# ProPrj_gzy_2025-03-24.net
KiCad netlist of a schematic drawn in EasyEDA Pro
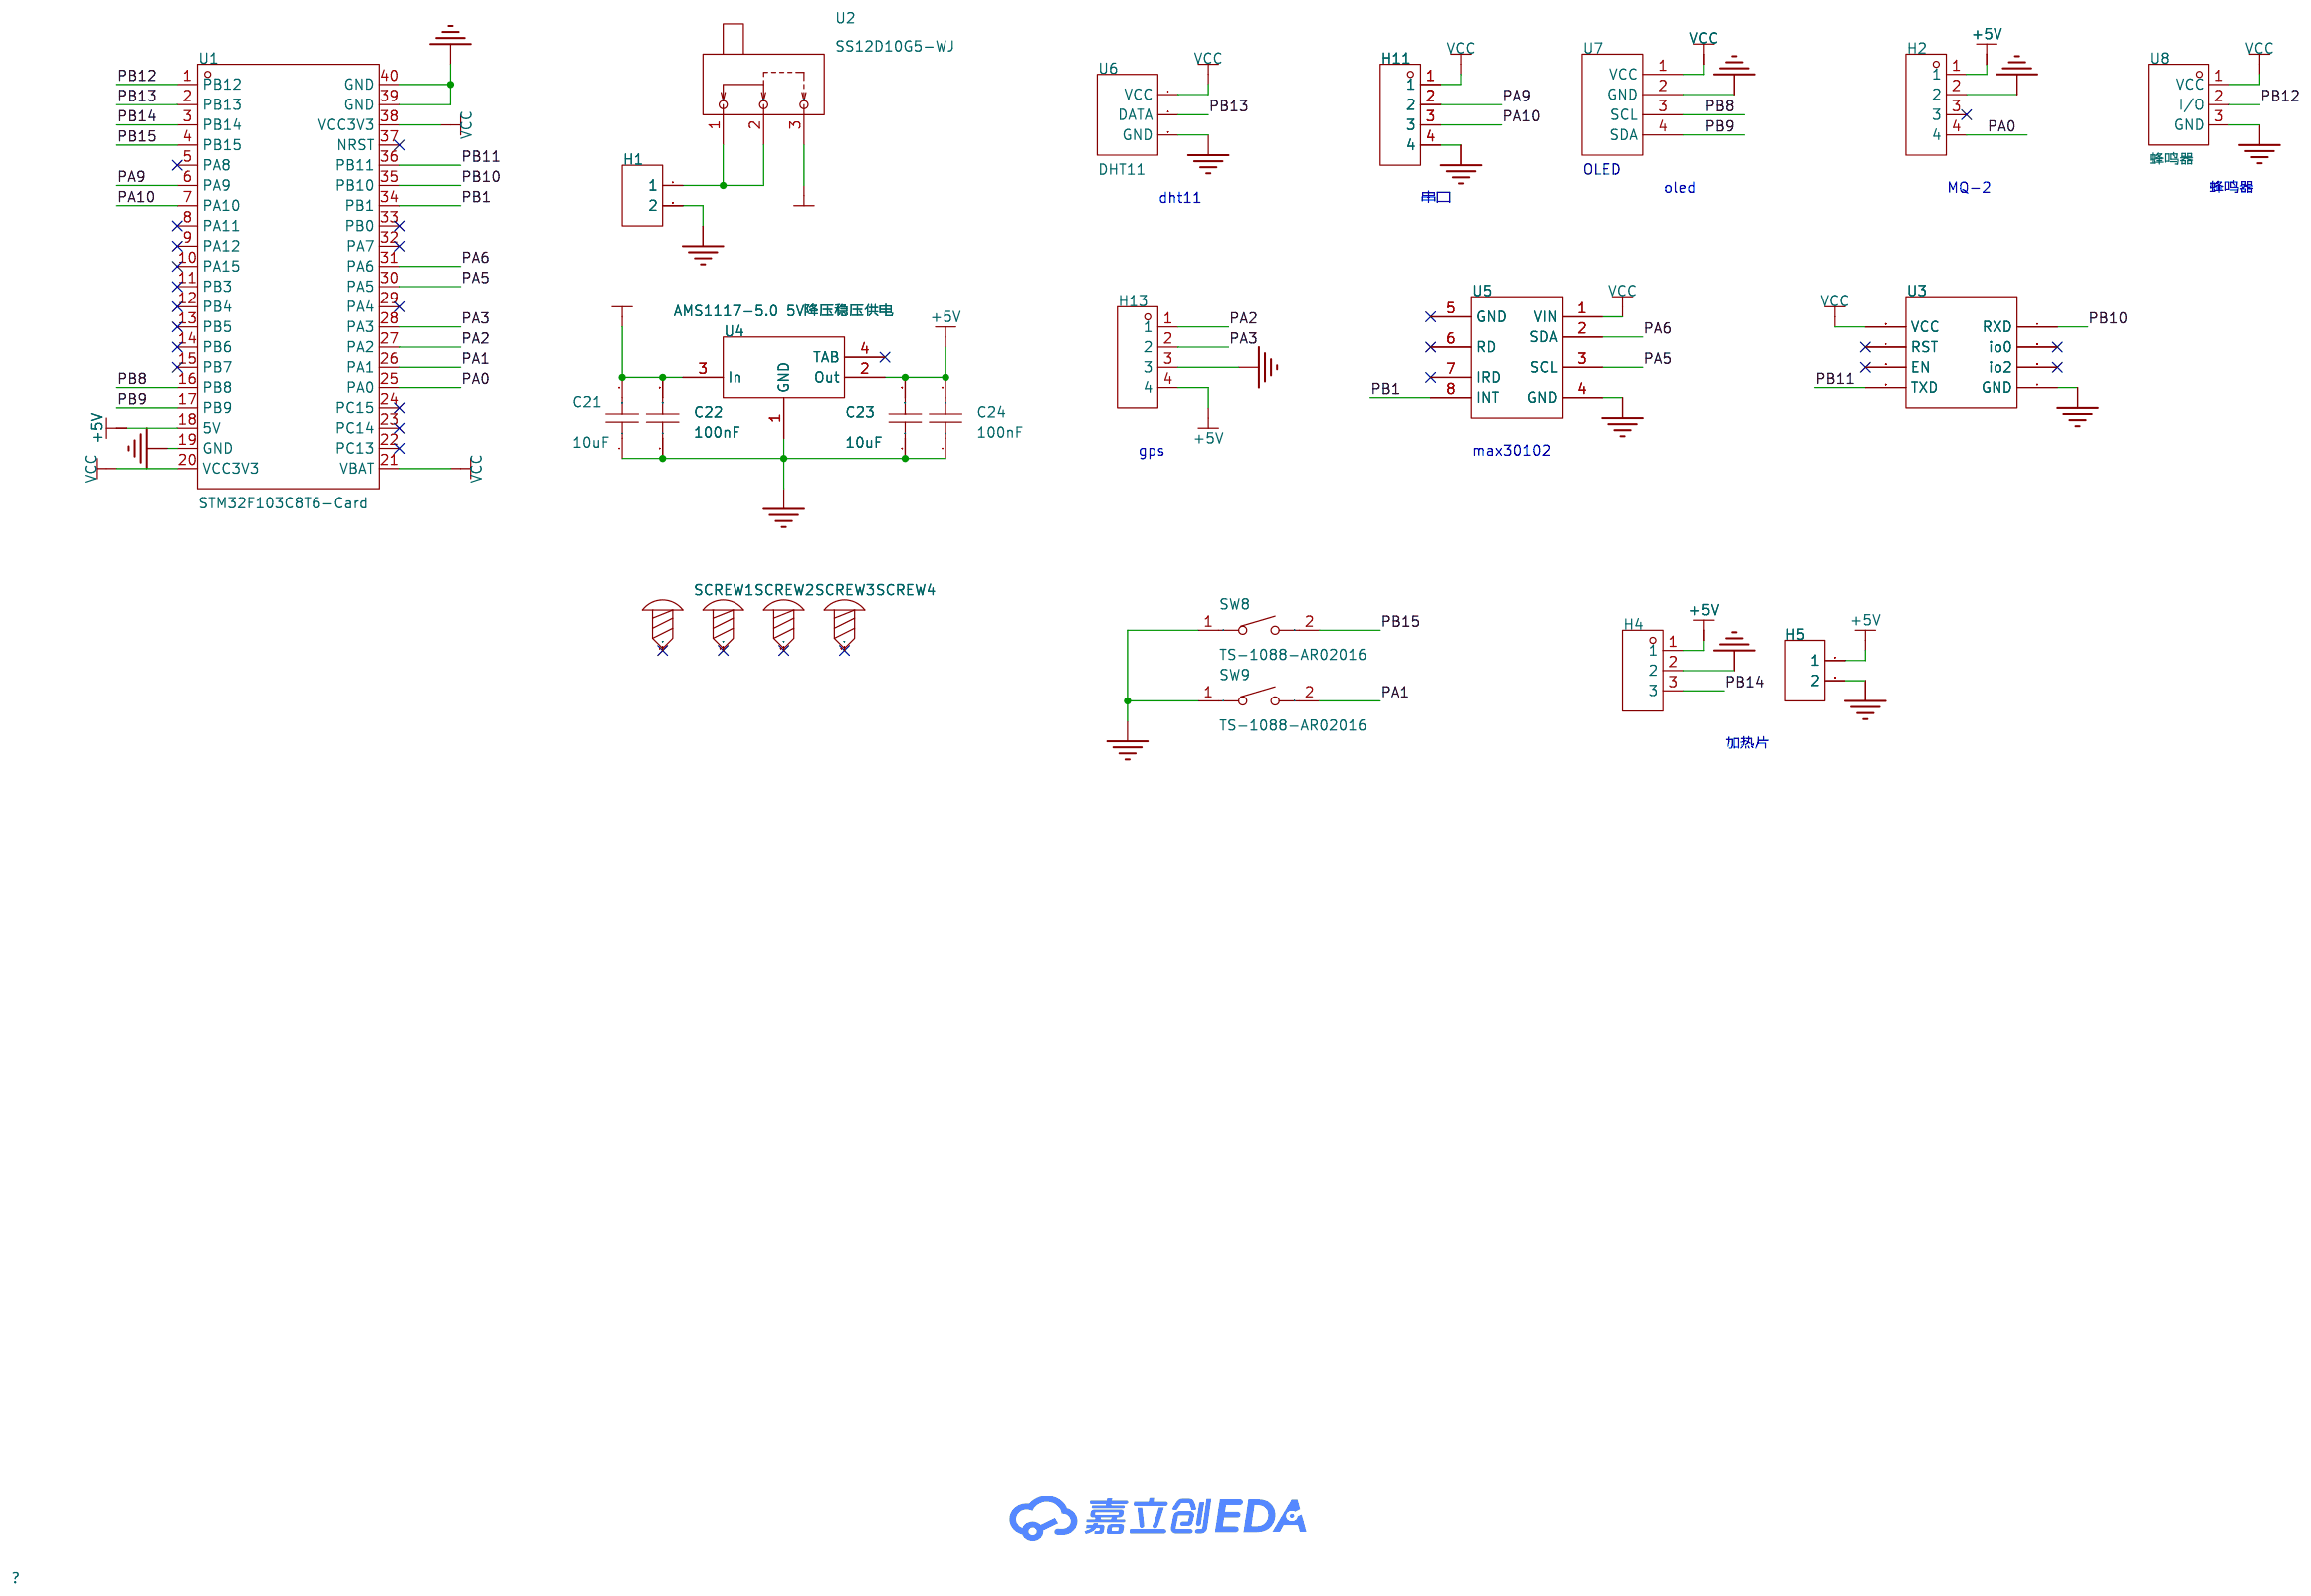
[diagram p0: schematic sheet]

(export (version "E")
  (design (tool "Eeschema 10.0.6"))
  (components
    (comp (ref "C21")
      (value "10uF")
      (footprint "easyedapro:C0805")
      (libsource (lib "easyedapro") (part "CapAcitance"))
    )
    (comp (ref "C22")
      (value "100nF")
      (footprint "easyedapro:C0805")
      (libsource (lib "easyedapro") (part "CapAcitance"))
    )
    (comp (ref "C23")
      (value "10uF")
      (footprint "easyedapro:C0805")
      (libsource (lib "easyedapro") (part "CapAcitance"))
    )
    (comp (ref "C24")
      (value "100nF")
      (footprint "easyedapro:C0805")
      (libsource (lib "easyedapro") (part "CapAcitance"))
    )
    (comp (ref "H1")
      (value "~")
      (footprint "easyedapro:HDR-TH_2P-P2.54-V-F")
      (libsource (lib "easyedapro") (part "Header-Female-2.54_1x2"))
    )
    (comp (ref "H2")
      (value "~")
      (footprint "easyedapro:HDR-TH_4P-P2.54-V-F")
      (libsource (lib "easyedapro") (part "2.54-1*4P母"))
    )
    (comp (ref "H4")
      (value "~")
      (footprint "easyedapro:HDR-TH_3P-P2.54-V-F")
      (libsource (lib "easyedapro") (part "PM254V-11-03-H85"))
    )
    (comp (ref "H5")
      (value "~")
      (footprint "easyedapro:HDR-TH_2P-P2.54-V-F")
      (libsource (lib "easyedapro") (part "Header-Female-2.54_1x2"))
    )
    (comp (ref "H11")
      (value "~")
      (footprint "easyedapro:HDR-TH_4P-P2.54-V-F")
      (libsource (lib "easyedapro") (part "2.54-1*4P母"))
    )
    (comp (ref "H13")
      (value "~")
      (footprint "easyedapro:HDR-TH_4P-P2.54-V-F")
      (libsource (lib "easyedapro") (part "2.54-1*4P母"))
    )
    (comp (ref "SCREW1")
      (value "~")
      (footprint "easyedapro:M3螺丝")
      (libsource (lib "easyedapro") (part "螺丝孔"))
    )
    (comp (ref "SCREW2")
      (value "~")
      (footprint "easyedapro:M3螺丝")
      (libsource (lib "easyedapro") (part "螺丝孔"))
    )
    (comp (ref "SCREW3")
      (value "~")
      (footprint "easyedapro:M3螺丝")
      (libsource (lib "easyedapro") (part "螺丝孔"))
    )
    (comp (ref "SCREW4")
      (value "~")
      (footprint "easyedapro:M3螺丝")
      (libsource (lib "easyedapro") (part "螺丝孔"))
    )
    (comp (ref "SW8")
      (value "TS-1088-AR02016")
      (footprint "easyedapro:SW-SMD_L3.9-W3.0-P4.45")
      (fields (field (name "Manufacturer") "XUNPU(讯普)"))
      (libsource (lib "easyedapro") (part "TS-1088-AR02016"))
    )
    (comp (ref "SW9")
      (value "TS-1088-AR02016")
      (footprint "easyedapro:SW-SMD_L3.9-W3.0-P4.45")
      (fields (field (name "Manufacturer") "XUNPU(讯普)"))
      (libsource (lib "easyedapro") (part "TS-1088-AR02016"))
    )
    (comp (ref "U1")
      (value "STM32F103C8T6-Card")
      (footprint "easyedapro:CONN-TH_L53.3-W22.9_STM32F103C8T6-CARD")
      (libsource (lib "easyedapro") (part "STM32F103C8T6-CARD"))
    )
    (comp (ref "U2")
      (value "SS12D10G5-WJ")
      (footprint "easyedapro:SW-TH_3P-SS12D06-1")
      (description "电路结构:单刀双掷;安装方式:直插;额定电流(DC):2A;额定电压(DC):125V;机械寿命:3千次;")
      (fields (field (name "Manufacturer") "SHOU HAN(首韩)"))
      (libsource (lib "easyedapro") (part "SS12D10G5-WJ"))
    )
    (comp (ref "U3")
      (value "~")
      (footprint "easyedapro:esp8266-01s")
      (description "esp8266-01swifi模块")
      (libsource (lib "easyedapro") (part "esp8266-01s"))
    )
    (comp (ref "U4")
      (value "AMS1117-5.0 5V降压稳压供电")
      (footprint "easyedapro:SOT-223_L6.5-W3.5-P2.30-LS7.0-BR")
      (fields (field (name "Manufacturer Part") "AMS1117-5.0") (field (name "Manufacturer") "AMS"))
      (libsource (lib "easyedapro") (part "AMS1117-5.0 5V降压稳压供电"))
    )
    (comp (ref "U5")
      (value "~")
      (footprint "easyedapro:MAX30102")
      (libsource (lib "easyedapro") (part "MAX30102"))
    )
    (comp (ref "U6")
      (value "DHT11")
      (footprint "easyedapro:DHT11_X")
      (libsource (lib "easyedapro") (part "DHT11"))
    )
    (comp (ref "U7")
      (value "~")
      (footprint "easyedapro:0.96OLED_4P")
      (libsource (lib "easyedapro") (part "OLED"))
    )
    (comp (ref "U8")
      (value "蜂鸣器")
      (footprint "easyedapro:蜂鸣器")
      (libsource (lib "easyedapro") (part "2.54MM间距单排插针3P/高度11MM"))
    )
  )
  (nets
    (net (code "1") (name "+5V") (class "Default")
      (node (ref "C23") (pin "2") (pinfunction "2_2") (pintype "input"))
      (node (ref "C24") (pin "2") (pinfunction "2_2") (pintype "input"))
      (node (ref "H13") (pin "4") (pinfunction "4_4") (pintype "unspecified"))
      (node (ref "H2") (pin "1") (pinfunction "1_1") (pintype "unspecified"))
      (node (ref "H4") (pin "1") (pinfunction "1_1") (pintype "unspecified"))
      (node (ref "H5") (pin "1") (pinfunction "1_1") (pintype "input"))
      (node (ref "U1") (pin "18") (pinfunction "5V_18") (pintype "unspecified"))
      (node (ref "U4") (pin "2") (pinfunction "Out_2") (pintype "input"))
    )
    (net (code "2") (name "+7V") (class "Default")
      (node (ref "C21") (pin "2") (pinfunction "2_2") (pintype "input"))
      (node (ref "C22") (pin "2") (pinfunction "2_2") (pintype "input"))
      (node (ref "U2") (pin "3") (pinfunction "3_3") (pintype "unspecified"))
      (node (ref "U4") (pin "3") (pinfunction "In_3") (pintype "input"))
    )
    (net (code "3") (name "/PA0") (class "Default")
      (node (ref "H2") (pin "4") (pinfunction "4_4") (pintype "unspecified"))
      (node (ref "U1") (pin "25") (pinfunction "PA0_25") (pintype "unspecified"))
    )
    (net (code "4") (name "/PA1") (class "Default")
      (node (ref "SW9") (pin "2") (pinfunction "2_2") (pintype "unspecified"))
      (node (ref "U1") (pin "26") (pinfunction "PA1_26") (pintype "unspecified"))
    )
    (net (code "5") (name "/PA2") (class "Default")
      (node (ref "H13") (pin "1") (pinfunction "1_1") (pintype "unspecified"))
      (node (ref "U1") (pin "27") (pinfunction "PA2_27") (pintype "unspecified"))
    )
    (net (code "6") (name "/PA3") (class "Default")
      (node (ref "H13") (pin "2") (pinfunction "2_2") (pintype "unspecified"))
      (node (ref "U1") (pin "28") (pinfunction "PA3_28") (pintype "unspecified"))
    )
    (net (code "7") (name "/PA5") (class "Default")
      (node (ref "U1") (pin "30") (pinfunction "PA5_30") (pintype "unspecified"))
      (node (ref "U5") (pin "3") (pinfunction "SCL_3") (pintype "input"))
    )
    (net (code "8") (name "/PA6") (class "Default")
      (node (ref "U1") (pin "31") (pinfunction "PA6_31") (pintype "unspecified"))
      (node (ref "U5") (pin "2") (pinfunction "SDA_2") (pintype "input"))
    )
    (net (code "9") (name "/PA9") (class "Default")
      (node (ref "H11") (pin "2") (pinfunction "2_2") (pintype "unspecified"))
      (node (ref "U1") (pin "6") (pinfunction "PA9_6") (pintype "unspecified"))
    )
    (net (code "10") (name "/PA10") (class "Default")
      (node (ref "H11") (pin "3") (pinfunction "3_3") (pintype "unspecified"))
      (node (ref "U1") (pin "7") (pinfunction "PA10_7") (pintype "unspecified"))
    )
    (net (code "11") (name "/PB1") (class "Default")
      (node (ref "U1") (pin "34") (pinfunction "PB1_34") (pintype "unspecified"))
      (node (ref "U5") (pin "8") (pinfunction "INT_8") (pintype "input"))
    )
    (net (code "12") (name "/PB8") (class "Default")
      (node (ref "U1") (pin "16") (pinfunction "PB8_16") (pintype "unspecified"))
      (node (ref "U7") (pin "3") (pinfunction "SCL_3") (pintype "input"))
    )
    (net (code "13") (name "/PB9") (class "Default")
      (node (ref "U1") (pin "17") (pinfunction "PB9_17") (pintype "unspecified"))
      (node (ref "U7") (pin "4") (pinfunction "SDA_4") (pintype "input"))
    )
    (net (code "14") (name "/PB10") (class "Default")
      (node (ref "U1") (pin "35") (pinfunction "PB10_35") (pintype "unspecified"))
      (node (ref "U3") (pin "4") (pinfunction "RXD_4") (pintype "input"))
    )
    (net (code "15") (name "/PB11") (class "Default")
      (node (ref "U1") (pin "36") (pinfunction "PB11_36") (pintype "unspecified"))
      (node (ref "U3") (pin "5") (pinfunction "TXD_5") (pintype "input"))
    )
    (net (code "16") (name "/PB12") (class "Default")
      (node (ref "U1") (pin "1") (pinfunction "PB12_1") (pintype "unspecified"))
      (node (ref "U8") (pin "2") (pinfunction "I/O_2") (pintype "input"))
    )
    (net (code "17") (name "/PB13") (class "Default")
      (node (ref "U1") (pin "2") (pinfunction "PB13_2") (pintype "unspecified"))
      (node (ref "U6") (pin "2") (pinfunction "DATA_2") (pintype "input"))
    )
    (net (code "18") (name "/PB14") (class "Default")
      (node (ref "H4") (pin "3") (pinfunction "3_3") (pintype "unspecified"))
      (node (ref "U1") (pin "3") (pinfunction "PB14_3") (pintype "unspecified"))
    )
    (net (code "19") (name "/PB15") (class "Default")
      (node (ref "SW8") (pin "2") (pinfunction "2_2") (pintype "unspecified"))
      (node (ref "U1") (pin "4") (pinfunction "PB15_4") (pintype "unspecified"))
    )
    (net (code "20") (name "GND") (class "Default")
      (node (ref "C21") (pin "1") (pinfunction "1_1") (pintype "input"))
      (node (ref "C22") (pin "1") (pinfunction "1_1") (pintype "input"))
      (node (ref "C23") (pin "1") (pinfunction "1_1") (pintype "input"))
      (node (ref "C24") (pin "1") (pinfunction "1_1") (pintype "input"))
      (node (ref "H1") (pin "2") (pinfunction "2_2") (pintype "input"))
      (node (ref "H11") (pin "4") (pinfunction "4_4") (pintype "unspecified"))
      (node (ref "H13") (pin "3") (pinfunction "3_3") (pintype "unspecified"))
      (node (ref "H2") (pin "2") (pinfunction "2_2") (pintype "unspecified"))
      (node (ref "H4") (pin "2") (pinfunction "2_2") (pintype "unspecified"))
      (node (ref "H5") (pin "2") (pinfunction "2_2") (pintype "input"))
      (node (ref "SW8") (pin "1") (pinfunction "1_1") (pintype "unspecified"))
      (node (ref "SW9") (pin "1") (pinfunction "1_1") (pintype "unspecified"))
      (node (ref "U1") (pin "19") (pinfunction "GND_19") (pintype "unspecified"))
      (node (ref "U1") (pin "39") (pinfunction "GND_39") (pintype "unspecified"))
      (node (ref "U1") (pin "40") (pinfunction "GND_40") (pintype "unspecified"))
      (node (ref "U3") (pin "1") (pinfunction "GND_1") (pintype "input"))
      (node (ref "U4") (pin "1") (pinfunction "GND_1") (pintype "input"))
      (node (ref "U5") (pin "4") (pinfunction "GND_4") (pintype "input"))
      (node (ref "U6") (pin "3") (pinfunction "GND_3") (pintype "input"))
      (node (ref "U7") (pin "2") (pinfunction "GND_2") (pintype "input"))
      (node (ref "U8") (pin "3") (pinfunction "GND_3") (pintype "input"))
    )
    (net (code "21") (name "Net-(H1-Pad1)") (class "Default")
      (node (ref "H1") (pin "1") (pinfunction "1_1") (pintype "input"))
      (node (ref "U2") (pin "1") (pinfunction "1_1") (pintype "unspecified"))
      (node (ref "U2") (pin "2") (pinfunction "2_2") (pintype "unspecified"))
    )
    (net (code "22") (name "VCC") (class "Default")
      (node (ref "H11") (pin "1") (pinfunction "1_1") (pintype "unspecified"))
      (node (ref "U1") (pin "20") (pinfunction "VCC3V3_20") (pintype "unspecified"))
      (node (ref "U1") (pin "21") (pinfunction "VBAT_21") (pintype "unspecified"))
      (node (ref "U1") (pin "38") (pinfunction "VCC3V3_38") (pintype "unspecified"))
      (node (ref "U3") (pin "8") (pinfunction "VCC_8") (pintype "input"))
      (node (ref "U5") (pin "1") (pinfunction "VIN_1") (pintype "input"))
      (node (ref "U6") (pin "1") (pinfunction "VCC_1") (pintype "input"))
      (node (ref "U7") (pin "1") (pinfunction "VCC_1") (pintype "input"))
      (node (ref "U8") (pin "1") (pinfunction "VCC_1") (pintype "input"))
    )
    (net (code "23") (name "unconnected-(H2-Pad3)") (class "Default")
      (node (ref "H2") (pin "3") (pinfunction "3_3") (pintype "unspecified+no_connect"))
    )
    (net (code "24") (name "unconnected-(SCREW1-Pad1)") (class "Default")
      (node (ref "SCREW1") (pin "1") (pinfunction "1_1") (pintype "input+no_connect"))
    )
    (net (code "25") (name "unconnected-(SCREW2-Pad1)") (class "Default")
      (node (ref "SCREW2") (pin "1") (pinfunction "1_1") (pintype "input+no_connect"))
    )
    (net (code "26") (name "unconnected-(SCREW3-Pad1)") (class "Default")
      (node (ref "SCREW3") (pin "1") (pinfunction "1_1") (pintype "input+no_connect"))
    )
    (net (code "27") (name "unconnected-(SCREW4-Pad1)") (class "Default")
      (node (ref "SCREW4") (pin "1") (pinfunction "1_1") (pintype "input+no_connect"))
    )
    (net (code "28") (name "unconnected-(U1-NRST-Pad37)") (class "Default")
      (node (ref "U1") (pin "37") (pinfunction "NRST_37") (pintype "unspecified+no_connect"))
    )
    (net (code "29") (name "unconnected-(U1-PA4-Pad29)") (class "Default")
      (node (ref "U1") (pin "29") (pinfunction "PA4_29") (pintype "unspecified+no_connect"))
    )
    (net (code "30") (name "unconnected-(U1-PA7-Pad32)") (class "Default")
      (node (ref "U1") (pin "32") (pinfunction "PA7_32") (pintype "unspecified+no_connect"))
    )
    (net (code "31") (name "unconnected-(U1-PA8-Pad5)") (class "Default")
      (node (ref "U1") (pin "5") (pinfunction "PA8_5") (pintype "unspecified+no_connect"))
    )
    (net (code "32") (name "unconnected-(U1-PA11-Pad8)") (class "Default")
      (node (ref "U1") (pin "8") (pinfunction "PA11_8") (pintype "unspecified+no_connect"))
    )
    (net (code "33") (name "unconnected-(U1-PA12-Pad9)") (class "Default")
      (node (ref "U1") (pin "9") (pinfunction "PA12_9") (pintype "unspecified+no_connect"))
    )
    (net (code "34") (name "unconnected-(U1-PA15-Pad10)") (class "Default")
      (node (ref "U1") (pin "10") (pinfunction "PA15_10") (pintype "unspecified+no_connect"))
    )
    (net (code "35") (name "unconnected-(U1-PB0-Pad33)") (class "Default")
      (node (ref "U1") (pin "33") (pinfunction "PB0_33") (pintype "unspecified+no_connect"))
    )
    (net (code "36") (name "unconnected-(U1-PB3-Pad11)") (class "Default")
      (node (ref "U1") (pin "11") (pinfunction "PB3_11") (pintype "unspecified+no_connect"))
    )
    (net (code "37") (name "unconnected-(U1-PB4-Pad12)") (class "Default")
      (node (ref "U1") (pin "12") (pinfunction "PB4_12") (pintype "unspecified+no_connect"))
    )
    (net (code "38") (name "unconnected-(U1-PB5-Pad13)") (class "Default")
      (node (ref "U1") (pin "13") (pinfunction "PB5_13") (pintype "unspecified+no_connect"))
    )
    (net (code "39") (name "unconnected-(U1-PB6-Pad14)") (class "Default")
      (node (ref "U1") (pin "14") (pinfunction "PB6_14") (pintype "unspecified+no_connect"))
    )
    (net (code "40") (name "unconnected-(U1-PB7-Pad15)") (class "Default")
      (node (ref "U1") (pin "15") (pinfunction "PB7_15") (pintype "unspecified+no_connect"))
    )
    (net (code "41") (name "unconnected-(U1-PC13-Pad22)") (class "Default")
      (node (ref "U1") (pin "22") (pinfunction "PC13_22") (pintype "unspecified+no_connect"))
    )
    (net (code "42") (name "unconnected-(U1-PC14-Pad23)") (class "Default")
      (node (ref "U1") (pin "23") (pinfunction "PC14_23") (pintype "unspecified+no_connect"))
    )
    (net (code "43") (name "unconnected-(U1-PC15-Pad24)") (class "Default")
      (node (ref "U1") (pin "24") (pinfunction "PC15_24") (pintype "unspecified+no_connect"))
    )
    (net (code "44") (name "unconnected-(U3-EN-Pad6)") (class "Default")
      (node (ref "U3") (pin "6") (pinfunction "EN_6") (pintype "input+no_connect"))
    )
    (net (code "45") (name "unconnected-(U3-RST-Pad7)") (class "Default")
      (node (ref "U3") (pin "7") (pinfunction "RST_7") (pintype "input+no_connect"))
    )
    (net (code "46") (name "unconnected-(U3-io0-Pad3)") (class "Default")
      (node (ref "U3") (pin "3") (pinfunction "io0_3") (pintype "input+no_connect"))
    )
    (net (code "47") (name "unconnected-(U3-io2-Pad2)") (class "Default")
      (node (ref "U3") (pin "2") (pinfunction "io2_2") (pintype "input+no_connect"))
    )
    (net (code "48") (name "unconnected-(U4-TAB-Pad4)") (class "Default")
      (node (ref "U4") (pin "4") (pinfunction "TAB_4") (pintype "input+no_connect"))
    )
    (net (code "49") (name "unconnected-(U5-GND-Pad5)") (class "Default")
      (node (ref "U5") (pin "5") (pinfunction "GND_5") (pintype "input+no_connect"))
    )
    (net (code "50") (name "unconnected-(U5-IRD-Pad7)") (class "Default")
      (node (ref "U5") (pin "7") (pinfunction "IRD_7") (pintype "input+no_connect"))
    )
    (net (code "51") (name "unconnected-(U5-RD-Pad6)") (class "Default")
      (node (ref "U5") (pin "6") (pinfunction "RD_6") (pintype "input+no_connect"))
    )
  )
)
